# Sheet1.net
KiCad netlist of a schematic drawn in Altium Designer
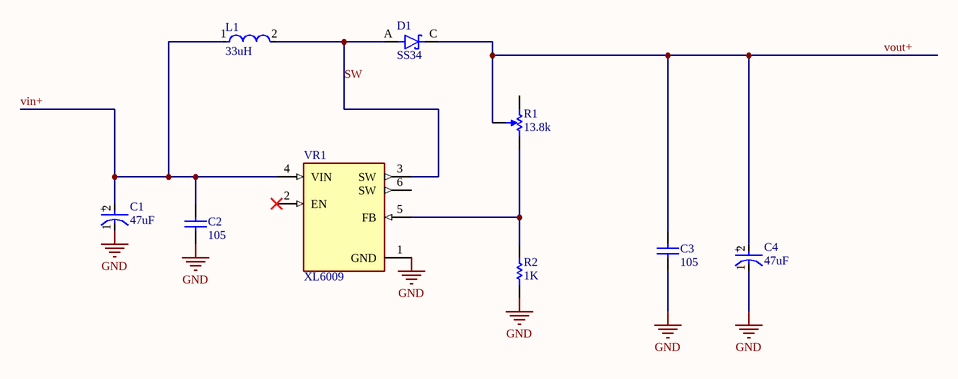
[diagram p0: Sheet1.SchDoc]

(export (version "E")
  (design (tool "Eeschema 10.0.6"))
  (components
    (comp (ref "C1")
      (value "47uF")
      (footprint "FP-FPD-MFG")
      (description "CAP ALUM 47UF 20% 35V SMD")
      (fields (field (name "TOLERANCE") "20%") (field (name "VOLTAGE") "35V"))
      (libsource (lib "Altium Content Vault") (part "cf48714ba7e38822c1575c7ec0b6d1f"))
    )
    (comp (ref "C2")
      (value "105")
      (footprint "CAPC1608X90X40ML10T20")
      (description "Chip Capacitor, 100 pF, +/- 5%, 50 V, -55 to 125 degC, 0603 (1608 Metric), RoHS, Tape and Reel")
      (fields (field (name "TOLERANCE") "5%") (field (name "VOLTAGE") "50V"))
      (libsource (lib "Altium Content Vault") (part "CAP-NP-2"))
    )
    (comp (ref "C3")
      (value "105")
      (footprint "CAPC1608X90X40ML10T20")
      (description "Chip Capacitor, 100 pF, +/- 5%, 50 V, -55 to 125 degC, 0603 (1608 Metric), RoHS, Tape and Reel")
      (fields (field (name "TOLERANCE") "5%") (field (name "VOLTAGE") "50V"))
      (libsource (lib "Altium Content Vault") (part "CAP-NP-2"))
    )
    (comp (ref "C4")
      (value "47uF")
      (footprint "FP-FPD-MFG")
      (description "CAP ALUM 47UF 20% 35V SMD")
      (fields (field (name "TOLERANCE") "20%") (field (name "VOLTAGE") "35V"))
      (libsource (lib "Altium Content Vault") (part "cf48714ba7e38822c1575c7ec0b6d1f"))
    )
    (comp (ref "D1")
      (value "SS34")
      (footprint "DIOM7959X265N")
      (description "Diode Schottky 40 V 3A Surface Mount SMC (DO-214AB)")
      (fields (field (name "MF") "ON Semiconductor"))
      (libsource (lib "Ongoing") (part "SS34"))
    )
    (comp (ref "L1")
      (value "33uH")
      (footprint "FP-LQH43CN_03-MFG")
      (description "Wire Wound Ferrite Inductor for General Circuits 10μH ±10% 0.56Ω 400mA 1812")
      (fields (field (name "TOLERANCE") "10%"))
      (libsource (lib "Altium Content Vault") (part "725321dda6339637d4d059423bc1c3c"))
    )
    (comp (ref "R1")
      (value "13.8k")
      (footprint "BOUR-3290W")
      (description "Trimming Potentiometer, 20 KOhm, 1 W, -65 to 150 degC, 3-Pin THD, RoHS, Tube")
      (fields (field (name "MANUFACTURER") "Bourns"))
      (libsource (lib "Altium Content Vault") (part "RES-ADJ-3_A"))
    )
    (comp (ref "R2")
      (value "1K")
      (footprint "RESC2013X60X35ML10T20")
      (description "Chip Resistor, 1 KOhm, +/- 1%, 125 mW, -55 to 155 degC, 0805 (2012 Metric), RoHS, Tape and Reel")
      (fields (field (name "TOLERANCE") "1%") (field (name "MANUFACTURER") "Yageo"))
      (libsource (lib "Altium Content Vault") (part "RES-2"))
    )
    (comp (ref "VR1")
      (value "XL6009")
      (footprint "DPAK170P1435X465-6N")
      (fields (field (name "MF") "XLSEMI"))
      (libsource (lib "Ongoing") (part "XL6009"))
    )
  )
  (nets
    (net (code "1") (name "/SW") (class "Default")
      (node (ref "D1") (pin "A") (pinfunction "A_A") (pintype "passive"))
      (node (ref "L1") (pin "2") (pinfunction "2_2") (pintype "passive"))
      (node (ref "VR1") (pin "3") (pinfunction "SW_3") (pintype "output"))
    )
    (net (code "2") (name "/vin+") (class "Default")
      (node (ref "C1") (pin "2") (pinfunction "A_2") (pintype "passive"))
      (node (ref "C2") (pin "2") (pinfunction "2_2") (pintype "passive"))
      (node (ref "L1") (pin "1") (pinfunction "1_1") (pintype "passive"))
      (node (ref "VR1") (pin "4") (pinfunction "VIN_4") (pintype "input"))
    )
    (net (code "3") (name "/vout+") (class "Default")
      (node (ref "C3") (pin "2") (pinfunction "2_2") (pintype "passive"))
      (node (ref "C4") (pin "2") (pinfunction "A_2") (pintype "passive"))
      (node (ref "D1") (pin "C") (pinfunction "K_C") (pintype "passive"))
      (node (ref "R1") (pin "2") (pinfunction "2_2") (pintype "passive"))
    )
    (net (code "4") (name "GND") (class "Default")
      (node (ref "C1") (pin "1") (pinfunction "C_1") (pintype "passive"))
      (node (ref "C2") (pin "1") (pinfunction "1_1") (pintype "passive"))
      (node (ref "C3") (pin "1") (pinfunction "1_1") (pintype "passive"))
      (node (ref "C4") (pin "1") (pinfunction "C_1") (pintype "passive"))
      (node (ref "R2") (pin "1") (pinfunction "1_1") (pintype "passive"))
      (node (ref "VR1") (pin "1") (pinfunction "GND_1") (pintype "power_in"))
    )
    (net (code "5") (name "Net-(VR1-FB)") (class "Default")
      (node (ref "R1") (pin "3") (pinfunction "3_3") (pintype "passive"))
      (node (ref "R2") (pin "2") (pinfunction "2_2") (pintype "passive"))
      (node (ref "VR1") (pin "5") (pinfunction "FB_5") (pintype "input"))
    )
    (net (code "6") (name "unconnected-(R1-Pad1)") (class "Default")
      (node (ref "R1") (pin "1") (pinfunction "1_1") (pintype "passive"))
    )
    (net (code "7") (name "unconnected-(VR1-EN-Pad2)") (class "Default")
      (node (ref "VR1") (pin "2") (pinfunction "EN_2") (pintype "input+no_connect"))
    )
    (net (code "8") (name "unconnected-(VR1-SW-Pad6)") (class "Default")
      (node (ref "VR1") (pin "6") (pinfunction "SW_6") (pintype "output"))
    )
  )
)
